# musIR-mk-1_0.net
KiCad netlist of a schematic drawn in EAGLE
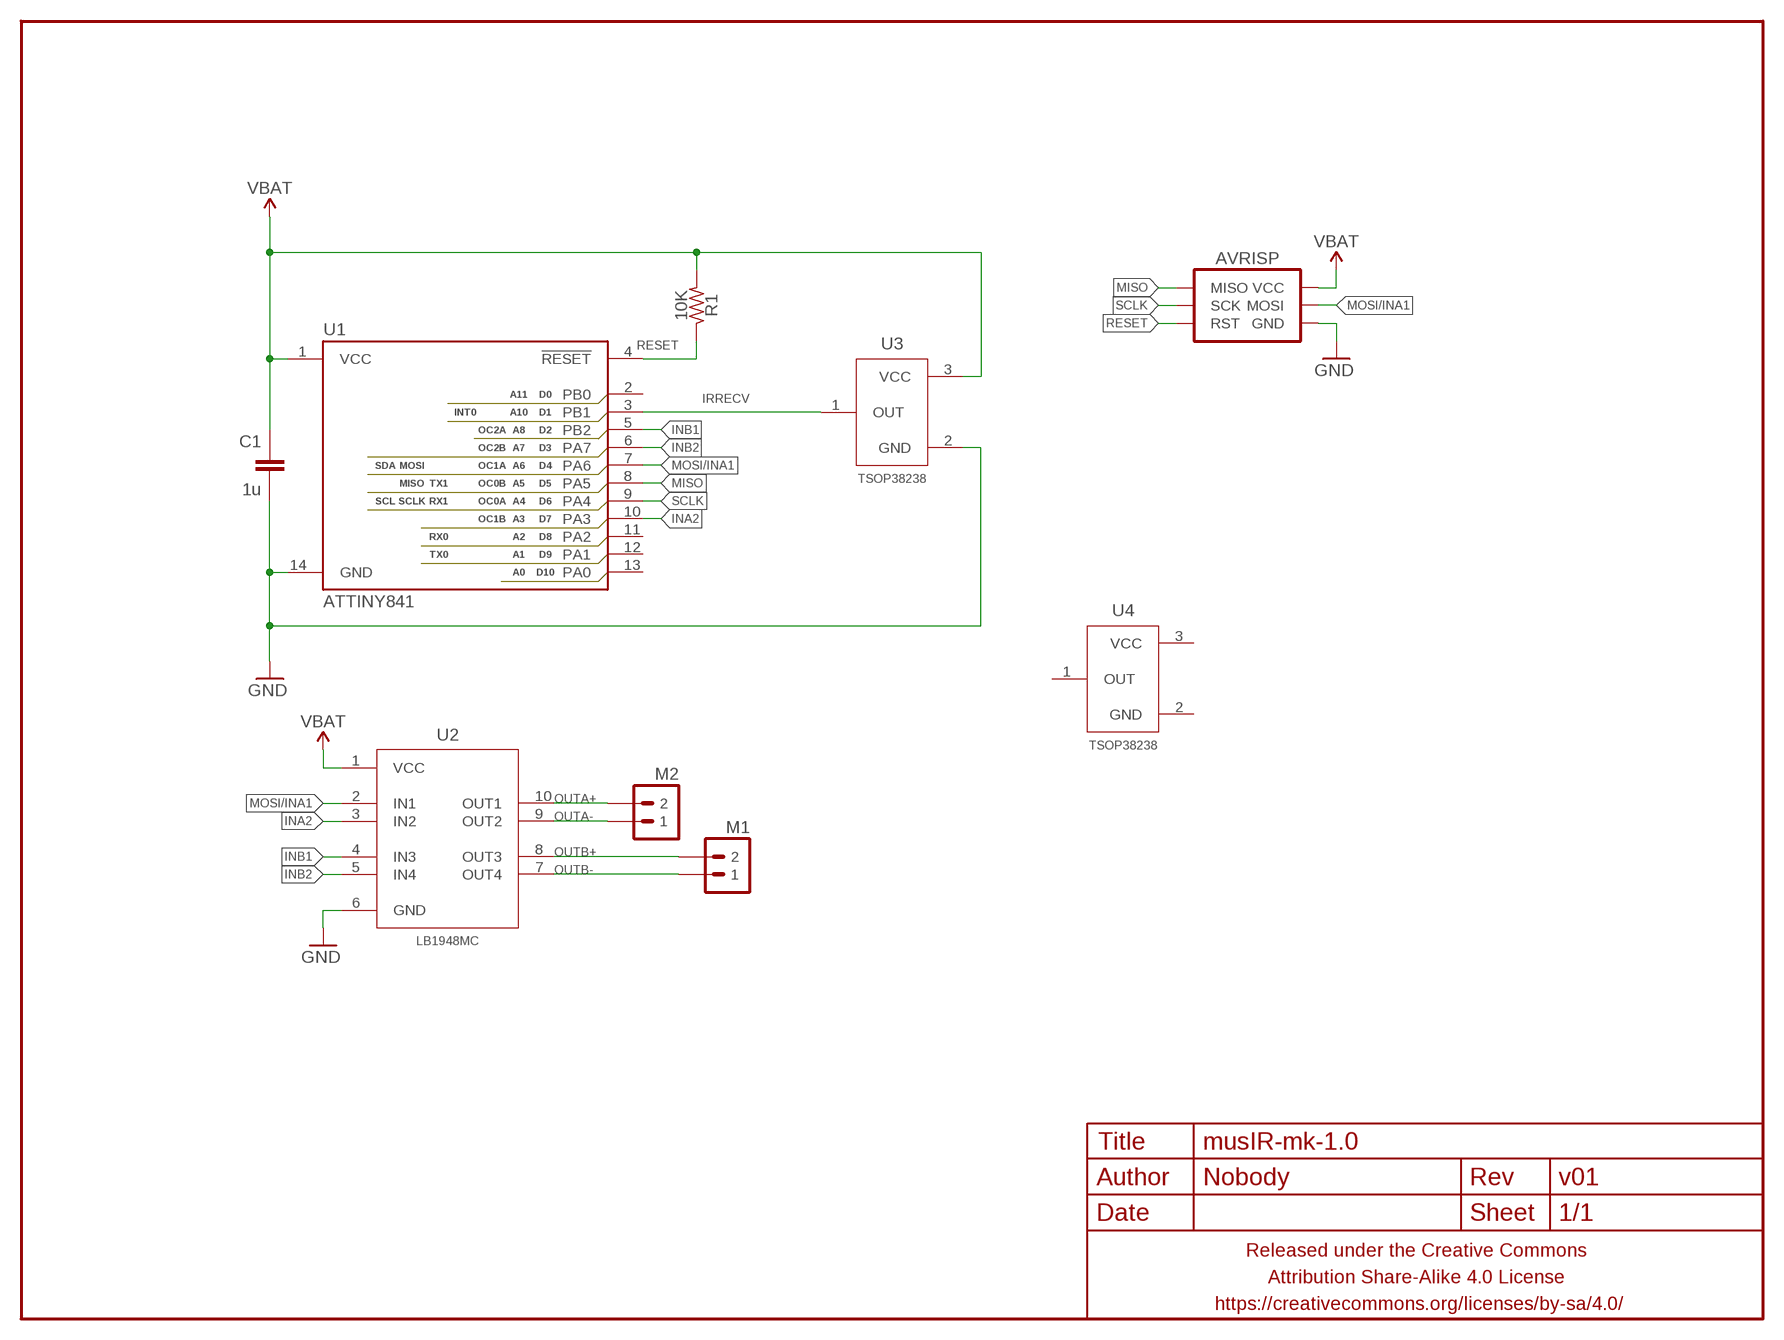
[diagram p0: schematic, sheet 1]

(export (version "E")
  (design (tool "Eeschema 10.0.6"))
  (components
    (comp (ref "AVRISP")
      (value "AVR_SPI_PRG_6TESTPOINTS")
      (footprint "eagle-import:2X3_TEST_POINTS")
      (libsource (lib "eagle-import") (part "AVR_SPI_PRG_6TESTPOINTS"))
    )
    (comp (ref "C1")
      (value "1u")
      (footprint "eagle-import:C0603-TIGHTER")
      (libsource (lib "eagle-import") (part "CAPACITOR-CERAMICC0603-TIGHTER"))
    )
    (comp (ref "FRAME1")
      (value "FRAME-LETTERNO_PACKAGE")
      (footprint "eagle-import:DUMMY")
      (fields (field (name "DESIGNER") "Nobody"))
      (libsource (lib "eagle-import") (part "FRAME-LETTERNO_PACKAGE"))
    )
    (comp (ref "M1")
      (value "M02PTH")
      (footprint "eagle-import:1X02")
      (libsource (lib "eagle-import") (part "M02PTH"))
    )
    (comp (ref "M2")
      (value "M02PTH")
      (footprint "eagle-import:1X02")
      (libsource (lib "eagle-import") (part "M02PTH"))
    )
    (comp (ref "R1")
      (value "10K")
      (footprint "eagle-import:R0603-TIGHTER")
      (libsource (lib "eagle-import") (part "RESISTORR0603-TIGHTER"))
    )
    (comp (ref "U1")
      (value "ATTINY841")
      (footprint "eagle-import:SO14")
      (libsource (lib "eagle-import") (part "ATTINY841SOIC14"))
    )
    (comp (ref "U2")
      (value "LB1948MC")
      (footprint "eagle-import:SO10-NOTREALLY")
      (libsource (lib "eagle-import") (part "LB1948MCMFP10SK"))
    )
    (comp (ref "U3")
      (value "TSOP38238")
      (footprint "eagle-import:TSOP38238")
      (libsource (lib "eagle-import") (part "TSOP382__/4__"))
    )
    (comp (ref "U4")
      (value "TSOP38238")
      (footprint "eagle-import:TSOP38238")
      (libsource (lib "eagle-import") (part "TSOP382__/4__"))
    )
  )
  (nets
    (net (code "1") (name "/IRRECV") (class "Default")
      (node (ref "U1") (pin "3") (pinfunction "PB1_3") (pintype "bidirectional"))
      (node (ref "U3") (pin "1") (pinfunction "OUT_1") (pintype "bidirectional"))
    )
    (net (code "2") (name "/OUTA+") (class "Default")
      (node (ref "M2") (pin "2") (pinfunction "2_2") (pintype "passive"))
      (node (ref "U2") (pin "10") (pinfunction "OUT1_10") (pintype "bidirectional"))
    )
    (net (code "3") (name "/OUTA-") (class "Default")
      (node (ref "M2") (pin "1") (pinfunction "1_1") (pintype "passive"))
      (node (ref "U2") (pin "9") (pinfunction "OUT2_9") (pintype "bidirectional"))
    )
    (net (code "4") (name "/OUTB+") (class "Default")
      (node (ref "M1") (pin "2") (pinfunction "2_2") (pintype "passive"))
      (node (ref "U2") (pin "8") (pinfunction "OUT3_8") (pintype "bidirectional"))
    )
    (net (code "5") (name "/OUTB-") (class "Default")
      (node (ref "M1") (pin "1") (pinfunction "1_1") (pintype "passive"))
      (node (ref "U2") (pin "7") (pinfunction "OUT4_7") (pintype "bidirectional"))
    )
    (net (code "6") (name "GND") (class "Default")
      (node (ref "AVRISP") (pin "6") (pinfunction "GND_6") (pintype "passive"))
      (node (ref "C1") (pin "2") (pinfunction "2_2") (pintype "passive"))
      (node (ref "U1") (pin "14") (pinfunction "GND_14") (pintype "bidirectional"))
      (node (ref "U2") (pin "6") (pinfunction "GND_6") (pintype "bidirectional"))
      (node (ref "U3") (pin "2") (pinfunction "GND_2") (pintype "bidirectional"))
    )
    (net (code "7") (name "INA2") (class "Default")
      (node (ref "U1") (pin "10") (pinfunction "PA3_10") (pintype "bidirectional"))
      (node (ref "U2") (pin "3") (pinfunction "IN2_3") (pintype "bidirectional"))
    )
    (net (code "8") (name "INB1") (class "Default")
      (node (ref "U1") (pin "5") (pinfunction "PB2_5") (pintype "bidirectional"))
      (node (ref "U2") (pin "4") (pinfunction "IN3_4") (pintype "bidirectional"))
    )
    (net (code "9") (name "INB2") (class "Default")
      (node (ref "U1") (pin "6") (pinfunction "PA7_6") (pintype "bidirectional"))
      (node (ref "U2") (pin "5") (pinfunction "IN4_5") (pintype "bidirectional"))
    )
    (net (code "10") (name "MISO") (class "Default")
      (node (ref "AVRISP") (pin "1") (pinfunction "MISO_1") (pintype "passive"))
      (node (ref "U1") (pin "8") (pinfunction "PA5_8") (pintype "bidirectional"))
    )
    (net (code "11") (name "MOSI{slash}INA1") (class "Default")
      (node (ref "AVRISP") (pin "4") (pinfunction "MOSI_4") (pintype "passive"))
      (node (ref "U1") (pin "7") (pinfunction "PA6_7") (pintype "bidirectional"))
      (node (ref "U2") (pin "2") (pinfunction "IN1_2") (pintype "bidirectional"))
    )
    (net (code "12") (name "RESET") (class "Default")
      (node (ref "AVRISP") (pin "5") (pinfunction "RST_5") (pintype "passive"))
      (node (ref "R1") (pin "1") (pinfunction "1_1") (pintype "passive"))
      (node (ref "U1") (pin "4") (pinfunction "~{RESET}_4") (pintype "bidirectional"))
    )
    (net (code "13") (name "SCLK") (class "Default")
      (node (ref "AVRISP") (pin "3") (pinfunction "SCK_3") (pintype "passive"))
      (node (ref "U1") (pin "9") (pinfunction "PA4_9") (pintype "bidirectional"))
    )
    (net (code "14") (name "VBAT") (class "Default")
      (node (ref "AVRISP") (pin "2") (pinfunction "VCC_2") (pintype "passive"))
      (node (ref "C1") (pin "1") (pinfunction "1_1") (pintype "passive"))
      (node (ref "R1") (pin "2") (pinfunction "2_2") (pintype "passive"))
      (node (ref "U1") (pin "1") (pinfunction "VCC_1") (pintype "bidirectional"))
      (node (ref "U2") (pin "1") (pinfunction "VCC_1") (pintype "bidirectional"))
      (node (ref "U3") (pin "3") (pinfunction "VCC_3") (pintype "bidirectional"))
    )
    (net (code "15") (name "unconnected-(U1-PA0-Pad13)") (class "Default")
      (node (ref "U1") (pin "13") (pinfunction "PA0_13") (pintype "bidirectional"))
    )
    (net (code "16") (name "unconnected-(U1-PA1-Pad12)") (class "Default")
      (node (ref "U1") (pin "12") (pinfunction "PA1_12") (pintype "bidirectional"))
    )
    (net (code "17") (name "unconnected-(U1-PA2-Pad11)") (class "Default")
      (node (ref "U1") (pin "11") (pinfunction "PA2_11") (pintype "bidirectional"))
    )
    (net (code "18") (name "unconnected-(U1-PB0-Pad2)") (class "Default")
      (node (ref "U1") (pin "2") (pinfunction "PB0_2") (pintype "bidirectional"))
    )
    (net (code "19") (name "unconnected-(U4-GND-Pad2)") (class "Default")
      (node (ref "U4") (pin "2") (pinfunction "GND_2") (pintype "bidirectional"))
    )
    (net (code "20") (name "unconnected-(U4-OUT-Pad1)") (class "Default")
      (node (ref "U4") (pin "1") (pinfunction "OUT_1") (pintype "bidirectional"))
    )
    (net (code "21") (name "unconnected-(U4-VCC-Pad3)") (class "Default")
      (node (ref "U4") (pin "3") (pinfunction "VCC_3") (pintype "bidirectional"))
    )
  )
)
